# 48V_Converter.net
KiCad netlist of a schematic drawn in Altium Designer
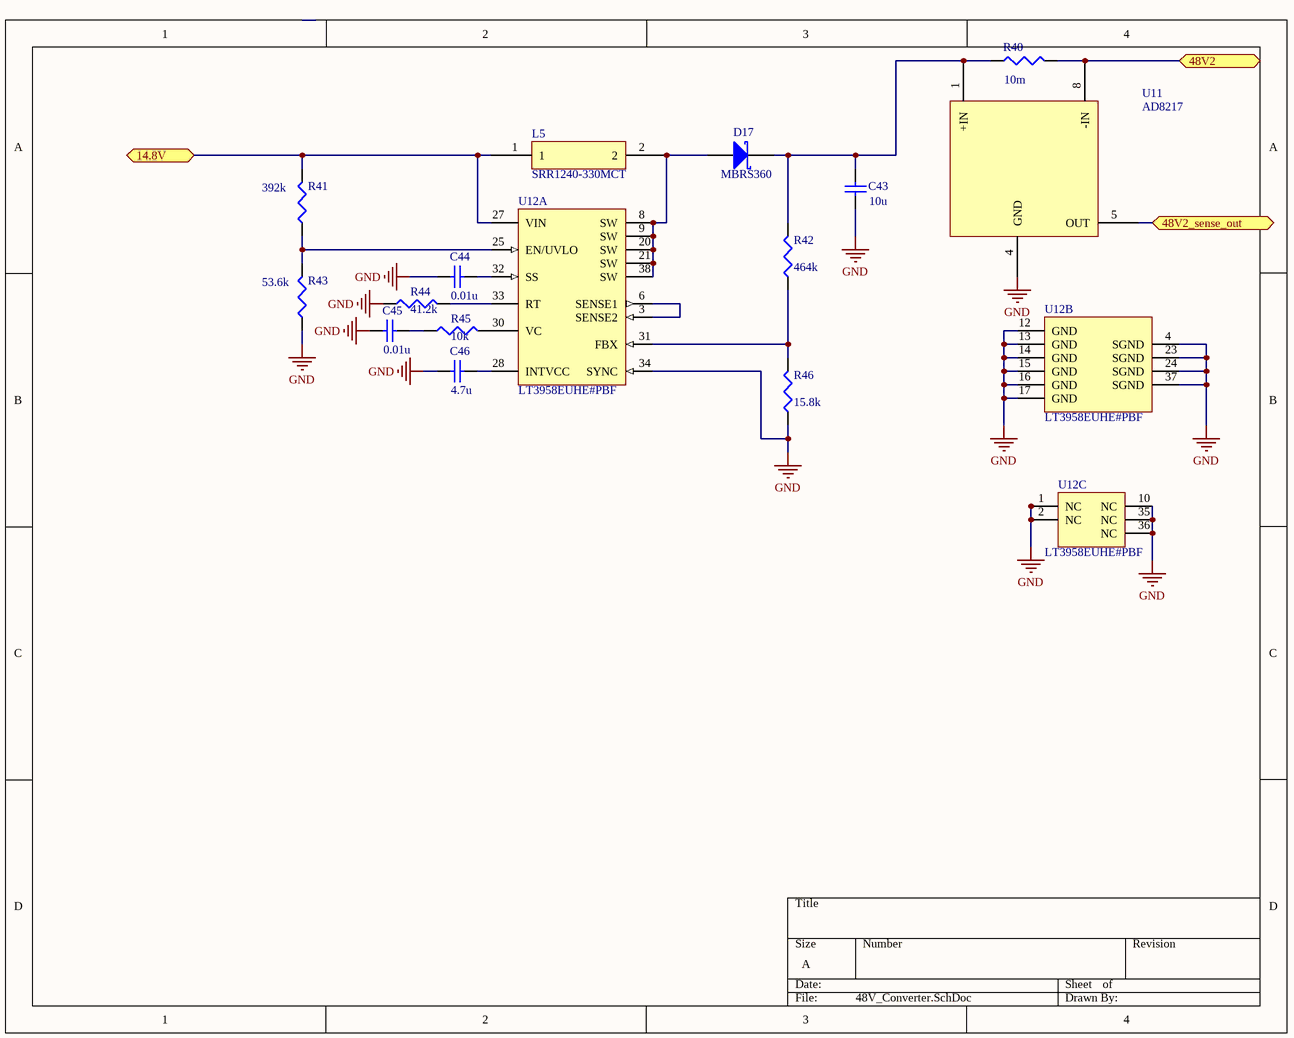
[diagram p0: 48V_Converter.SchDoc]

(export (version "E")
  (design (tool "Eeschema 10.0.6"))
  (components
    (comp (ref "C43")
      (value "10u")
      (footprint "C1206")
      (description "Capacitor (Semiconductor SIM Model)")
      (fields (field (name "Comment") "Cap Semi") (field (name "PUBLISHER") "Altium Limited"))
      (libsource (lib "Miscellaneous Devices") (part "Cap Semi"))
    )
    (comp (ref "C44")
      (value "0.01u")
      (footprint "C1206")
      (description "Capacitor (Semiconductor SIM Model)")
      (fields (field (name "Comment") "Cap Semi") (field (name "PUBLISHER") "Altium Limited"))
      (libsource (lib "Miscellaneous Devices") (part "Cap Semi"))
    )
    (comp (ref "C45")
      (value "0.01u")
      (footprint "C1206")
      (description "Capacitor (Semiconductor SIM Model)")
      (fields (field (name "Comment") "Cap Semi") (field (name "PUBLISHER") "Altium Limited"))
      (libsource (lib "Miscellaneous Devices") (part "Cap Semi"))
    )
    (comp (ref "C46")
      (value "4.7u")
      (footprint "C1206")
      (description "Capacitor (Semiconductor SIM Model)")
      (fields (field (name "Comment") "Cap Semi") (field (name "PUBLISHER") "Altium Limited"))
      (libsource (lib "Miscellaneous Devices") (part "Cap Semi"))
    )
    (comp (ref "D17")
      (value "MBRS360")
      (footprint "SMB")
      (description "Schottky Diode")
      (fields (field (name "PUBLISHER") "Altium Limited"))
      (libsource (lib "Miscellaneous Devices") (part "D Schottky"))
    )
    (comp (ref "L5")
      (value "SRR1240-330MCT")
      (footprint "SRR1240-4R7M")
      (description "Inductor")
      (libsource (lib "Power_Board_Parts_Library_Final") (part "SRR1240-4R7MCT"))
    )
    (comp (ref "R40")
      (value "10m")
      (footprint "J1-0603")
      (description "Resistor")
      (fields (field (name "Comment") "Res3") (field (name "PUBLISHER") "Altium Limited"))
      (libsource (lib "Miscellaneous Devices") (part "Res3"))
    )
    (comp (ref "R41")
      (value "392k")
      (footprint "J1-0603")
      (description "Resistor")
      (fields (field (name "Comment") "Res3") (field (name "PUBLISHER") "Altium Limited"))
      (libsource (lib "Miscellaneous Devices") (part "Res3"))
    )
    (comp (ref "R42")
      (value "464k")
      (footprint "J1-0603")
      (description "Resistor")
      (fields (field (name "Comment") "Res3") (field (name "PUBLISHER") "Altium Limited"))
      (libsource (lib "Miscellaneous Devices") (part "Res3"))
    )
    (comp (ref "R43")
      (value "53.6k")
      (footprint "J1-0603")
      (description "Resistor")
      (fields (field (name "Comment") "Res3") (field (name "PUBLISHER") "Altium Limited"))
      (libsource (lib "Miscellaneous Devices") (part "Res3"))
    )
    (comp (ref "R44")
      (value "41.2k")
      (footprint "J1-0603")
      (description "Resistor")
      (fields (field (name "Comment") "Res3") (field (name "PUBLISHER") "Altium Limited"))
      (libsource (lib "Miscellaneous Devices") (part "Res3"))
    )
    (comp (ref "R45")
      (value "10k")
      (footprint "J1-0603")
      (description "Resistor")
      (fields (field (name "Comment") "Res3") (field (name "PUBLISHER") "Altium Limited"))
      (libsource (lib "Miscellaneous Devices") (part "Res3"))
    )
    (comp (ref "R46")
      (value "15.8k")
      (footprint "J1-0603")
      (description "Resistor")
      (fields (field (name "Comment") "Res3") (field (name "PUBLISHER") "Altium Limited"))
      (libsource (lib "Miscellaneous Devices") (part "Res3"))
    )
    (comp (ref "U11")
      (value "AD8217")
      (footprint "AD8217")
      (description "Current Shunt Moniter")
      (libsource (lib "Integrated_Library") (part "AD8217"))
    )
    (comp (ref "U12")
      (value "LT3958EUHE#PBF")
      (footprint "LT3958")
      (description "LT3958")
      (fields (field (name "MANUFACTURER") "Linear Technology"))
      (libsource (lib "Integrated_Library") (part "LT3958EUHE#PBF"))
    )
  )
  (nets
    (net (code "1") (name "/14.8V") (class "Default")
      (node (ref "L5") (pin "1") (pinfunction "1_1") (pintype "passive"))
      (node (ref "R41") (pin "2") (pinfunction "2_2") (pintype "passive"))
      (node (ref "U12") (pin "27") (pinfunction "VIN_27") (pintype "power_in"))
    )
    (net (code "2") (name "/48V2") (class "Default")
      (node (ref "R40") (pin "2") (pinfunction "2_2") (pintype "passive"))
      (node (ref "U11") (pin "8") (pinfunction "-IN_8") (pintype "passive"))
    )
    (net (code "3") (name "/48V2_sense_out") (class "Default")
      (node (ref "U11") (pin "5") (pinfunction "OUT_5") (pintype "passive"))
    )
    (net (code "4") (name "GND") (class "Default")
      (node (ref "C43") (pin "1") (pinfunction "1_1") (pintype "passive"))
      (node (ref "C44") (pin "1") (pinfunction "1_1") (pintype "passive"))
      (node (ref "C45") (pin "1") (pinfunction "1_1") (pintype "passive"))
      (node (ref "C46") (pin "1") (pinfunction "1_1") (pintype "passive"))
      (node (ref "R43") (pin "1") (pinfunction "1_1") (pintype "passive"))
      (node (ref "R44") (pin "1") (pinfunction "1_1") (pintype "passive"))
      (node (ref "R46") (pin "1") (pinfunction "1_1") (pintype "passive"))
      (node (ref "U11") (pin "4") (pinfunction "GND_4") (pintype "passive"))
      (node (ref "U12") (pin "1") (pinfunction "NC_1") (pintype "passive"))
      (node (ref "U12") (pin "10") (pinfunction "NC_10") (pintype "passive"))
      (node (ref "U12") (pin "12") (pinfunction "GND_12") (pintype "power_in"))
      (node (ref "U12") (pin "13") (pinfunction "GND_13") (pintype "power_in"))
      (node (ref "U12") (pin "14") (pinfunction "GND_14") (pintype "power_in"))
      (node (ref "U12") (pin "15") (pinfunction "GND_15") (pintype "power_in"))
      (node (ref "U12") (pin "16") (pinfunction "GND_16") (pintype "power_in"))
      (node (ref "U12") (pin "17") (pinfunction "GND_17") (pintype "power_in"))
      (node (ref "U12") (pin "2") (pinfunction "NC_2") (pintype "passive"))
      (node (ref "U12") (pin "23") (pinfunction "SGND_23") (pintype "power_in"))
      (node (ref "U12") (pin "24") (pinfunction "SGND_24") (pintype "power_in"))
      (node (ref "U12") (pin "34") (pinfunction "SYNC_34") (pintype "input"))
      (node (ref "U12") (pin "35") (pinfunction "NC_35") (pintype "passive"))
      (node (ref "U12") (pin "36") (pinfunction "NC_36") (pintype "passive"))
      (node (ref "U12") (pin "37") (pinfunction "SGND_37") (pintype "power_in"))
      (node (ref "U12") (pin "4") (pinfunction "SGND_4") (pintype "power_in"))
    )
    (net (code "5") (name "Net-(C45-Pad2)") (class "Default")
      (node (ref "C45") (pin "2") (pinfunction "2_2") (pintype "passive"))
      (node (ref "R45") (pin "1") (pinfunction "1_1") (pintype "passive"))
    )
    (net (code "6") (name "Net-(D17-A)") (class "Default")
      (node (ref "D17") (pin "1") (pinfunction "A_1") (pintype "passive"))
      (node (ref "L5") (pin "2") (pinfunction "2_2") (pintype "passive"))
      (node (ref "U12") (pin "20") (pinfunction "SW_20") (pintype "power_in"))
      (node (ref "U12") (pin "21") (pinfunction "SW_21") (pintype "power_in"))
      (node (ref "U12") (pin "38") (pinfunction "SW_38") (pintype "power_in"))
      (node (ref "U12") (pin "8") (pinfunction "SW_8") (pintype "power_in"))
      (node (ref "U12") (pin "9") (pinfunction "SW_9") (pintype "power_in"))
    )
    (net (code "7") (name "Net-(D17-K)") (class "Default")
      (node (ref "C43") (pin "2") (pinfunction "2_2") (pintype "passive"))
      (node (ref "D17") (pin "2") (pinfunction "K_2") (pintype "passive"))
      (node (ref "R40") (pin "1") (pinfunction "1_1") (pintype "passive"))
      (node (ref "R42") (pin "2") (pinfunction "2_2") (pintype "passive"))
      (node (ref "U11") (pin "1") (pinfunction "+IN_1") (pintype "passive"))
    )
    (net (code "8") (name "Net-(U12A-EN{slash}UVLO)") (class "Default")
      (node (ref "R41") (pin "1") (pinfunction "1_1") (pintype "passive"))
      (node (ref "R43") (pin "2") (pinfunction "2_2") (pintype "passive"))
      (node (ref "U12") (pin "25") (pinfunction "EN/UVLO_25") (pintype "input"))
    )
    (net (code "9") (name "Net-(U12A-FBX)") (class "Default")
      (node (ref "R42") (pin "1") (pinfunction "1_1") (pintype "passive"))
      (node (ref "R46") (pin "2") (pinfunction "2_2") (pintype "passive"))
      (node (ref "U12") (pin "31") (pinfunction "FBX_31") (pintype "input"))
    )
    (net (code "10") (name "Net-(U12A-INTVCC)") (class "Default")
      (node (ref "C46") (pin "2") (pinfunction "2_2") (pintype "passive"))
      (node (ref "U12") (pin "28") (pinfunction "INTVCC_28") (pintype "power_in"))
    )
    (net (code "11") (name "Net-(U12A-RT)") (class "Default")
      (node (ref "R44") (pin "2") (pinfunction "2_2") (pintype "passive"))
      (node (ref "U12") (pin "33") (pinfunction "RT_33") (pintype "passive"))
    )
    (net (code "12") (name "Net-(U12A-SENSE1)") (class "Default")
      (node (ref "U12") (pin "3") (pinfunction "SENSE2_3") (pintype "input"))
      (node (ref "U12") (pin "6") (pinfunction "SENSE1_6") (pintype "output"))
    )
    (net (code "13") (name "Net-(U12A-SS)") (class "Default")
      (node (ref "C44") (pin "2") (pinfunction "2_2") (pintype "passive"))
      (node (ref "U12") (pin "32") (pinfunction "SS_32") (pintype "input"))
    )
    (net (code "14") (name "Net-(U12A-VC)") (class "Default")
      (node (ref "R45") (pin "2") (pinfunction "2_2") (pintype "passive"))
      (node (ref "U12") (pin "30") (pinfunction "VC_30") (pintype "passive"))
    )
  )
)
